# MultiWiiChassis_quadlite_power.net
KiCad netlist of a schematic drawn in EAGLE
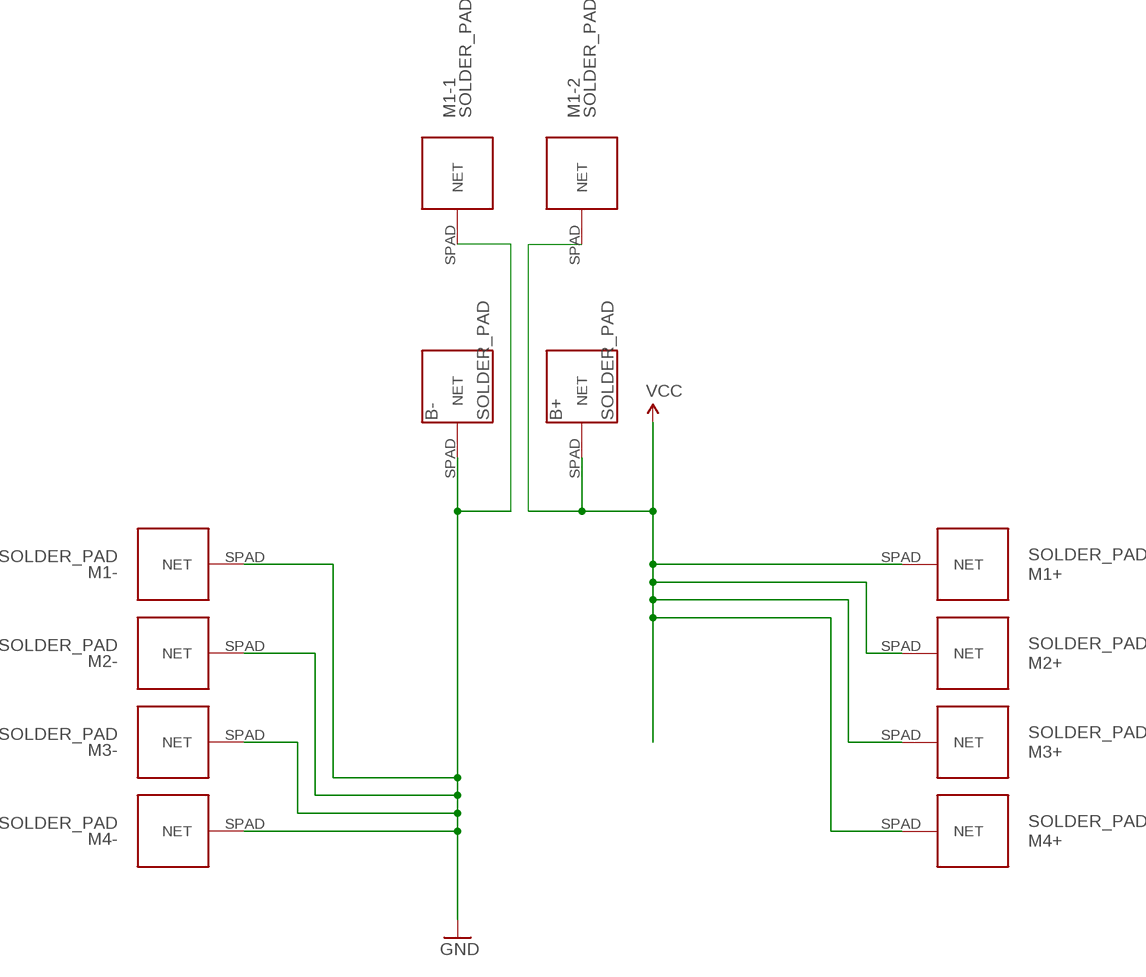
[diagram p0: schematic, sheet 1]

(export (version "E")
  (design (tool "Eeschema 10.0.6"))
  (components
    (comp (ref "B+")
      (value "SOLDER_PAD")
      (footprint "eagle-import:SOLDER_PAD")
      (libsource (lib "eagle-import") (part "SOLDER_PAD"))
    )
    (comp (ref "B-")
      (value "SOLDER_PAD")
      (footprint "eagle-import:SOLDER_PAD")
      (libsource (lib "eagle-import") (part "SOLDER_PAD"))
    )
    (comp (ref "M1+")
      (value "SOLDER_PAD")
      (footprint "eagle-import:SOLDER_PAD")
      (libsource (lib "eagle-import") (part "SOLDER_PAD"))
    )
    (comp (ref "M1-")
      (value "SOLDER_PAD")
      (footprint "eagle-import:SOLDER_PAD")
      (libsource (lib "eagle-import") (part "SOLDER_PAD"))
    )
    (comp (ref "M1-1")
      (value "SOLDER_PAD")
      (footprint "eagle-import:SOLDER_PAD")
      (libsource (lib "eagle-import") (part "SOLDER_PAD"))
    )
    (comp (ref "M1-2")
      (value "SOLDER_PAD")
      (footprint "eagle-import:SOLDER_PAD")
      (libsource (lib "eagle-import") (part "SOLDER_PAD"))
    )
    (comp (ref "M2+")
      (value "SOLDER_PAD")
      (footprint "eagle-import:SOLDER_PAD")
      (libsource (lib "eagle-import") (part "SOLDER_PAD"))
    )
    (comp (ref "M2-")
      (value "SOLDER_PAD")
      (footprint "eagle-import:SOLDER_PAD")
      (libsource (lib "eagle-import") (part "SOLDER_PAD"))
    )
    (comp (ref "M3+")
      (value "SOLDER_PAD")
      (footprint "eagle-import:SOLDER_PAD")
      (libsource (lib "eagle-import") (part "SOLDER_PAD"))
    )
    (comp (ref "M3-")
      (value "SOLDER_PAD")
      (footprint "eagle-import:SOLDER_PAD")
      (libsource (lib "eagle-import") (part "SOLDER_PAD"))
    )
    (comp (ref "M4+")
      (value "SOLDER_PAD")
      (footprint "eagle-import:SOLDER_PAD")
      (libsource (lib "eagle-import") (part "SOLDER_PAD"))
    )
    (comp (ref "M4-")
      (value "SOLDER_PAD")
      (footprint "eagle-import:SOLDER_PAD")
      (libsource (lib "eagle-import") (part "SOLDER_PAD"))
    )
  )
  (nets
    (net (code "1") (name "GND") (class "Default")
      (node (ref "B-") (pin "SPAD") (pinfunction "NET_SPAD") (pintype "bidirectional"))
      (node (ref "M1-") (pin "SPAD") (pinfunction "NET_SPAD") (pintype "bidirectional"))
      (node (ref "M1-1") (pin "SPAD") (pinfunction "NET_SPAD") (pintype "bidirectional"))
      (node (ref "M2-") (pin "SPAD") (pinfunction "NET_SPAD") (pintype "bidirectional"))
      (node (ref "M3-") (pin "SPAD") (pinfunction "NET_SPAD") (pintype "bidirectional"))
      (node (ref "M4-") (pin "SPAD") (pinfunction "NET_SPAD") (pintype "bidirectional"))
    )
    (net (code "2") (name "VCC") (class "Default")
      (node (ref "B+") (pin "SPAD") (pinfunction "NET_SPAD") (pintype "bidirectional"))
      (node (ref "M1+") (pin "SPAD") (pinfunction "NET_SPAD") (pintype "bidirectional"))
      (node (ref "M1-2") (pin "SPAD") (pinfunction "NET_SPAD") (pintype "bidirectional"))
      (node (ref "M2+") (pin "SPAD") (pinfunction "NET_SPAD") (pintype "bidirectional"))
      (node (ref "M3+") (pin "SPAD") (pinfunction "NET_SPAD") (pintype "bidirectional"))
      (node (ref "M4+") (pin "SPAD") (pinfunction "NET_SPAD") (pintype "bidirectional"))
    )
  )
)
